# pedalBoard.net
KiCad netlist of a schematic drawn in EAGLE
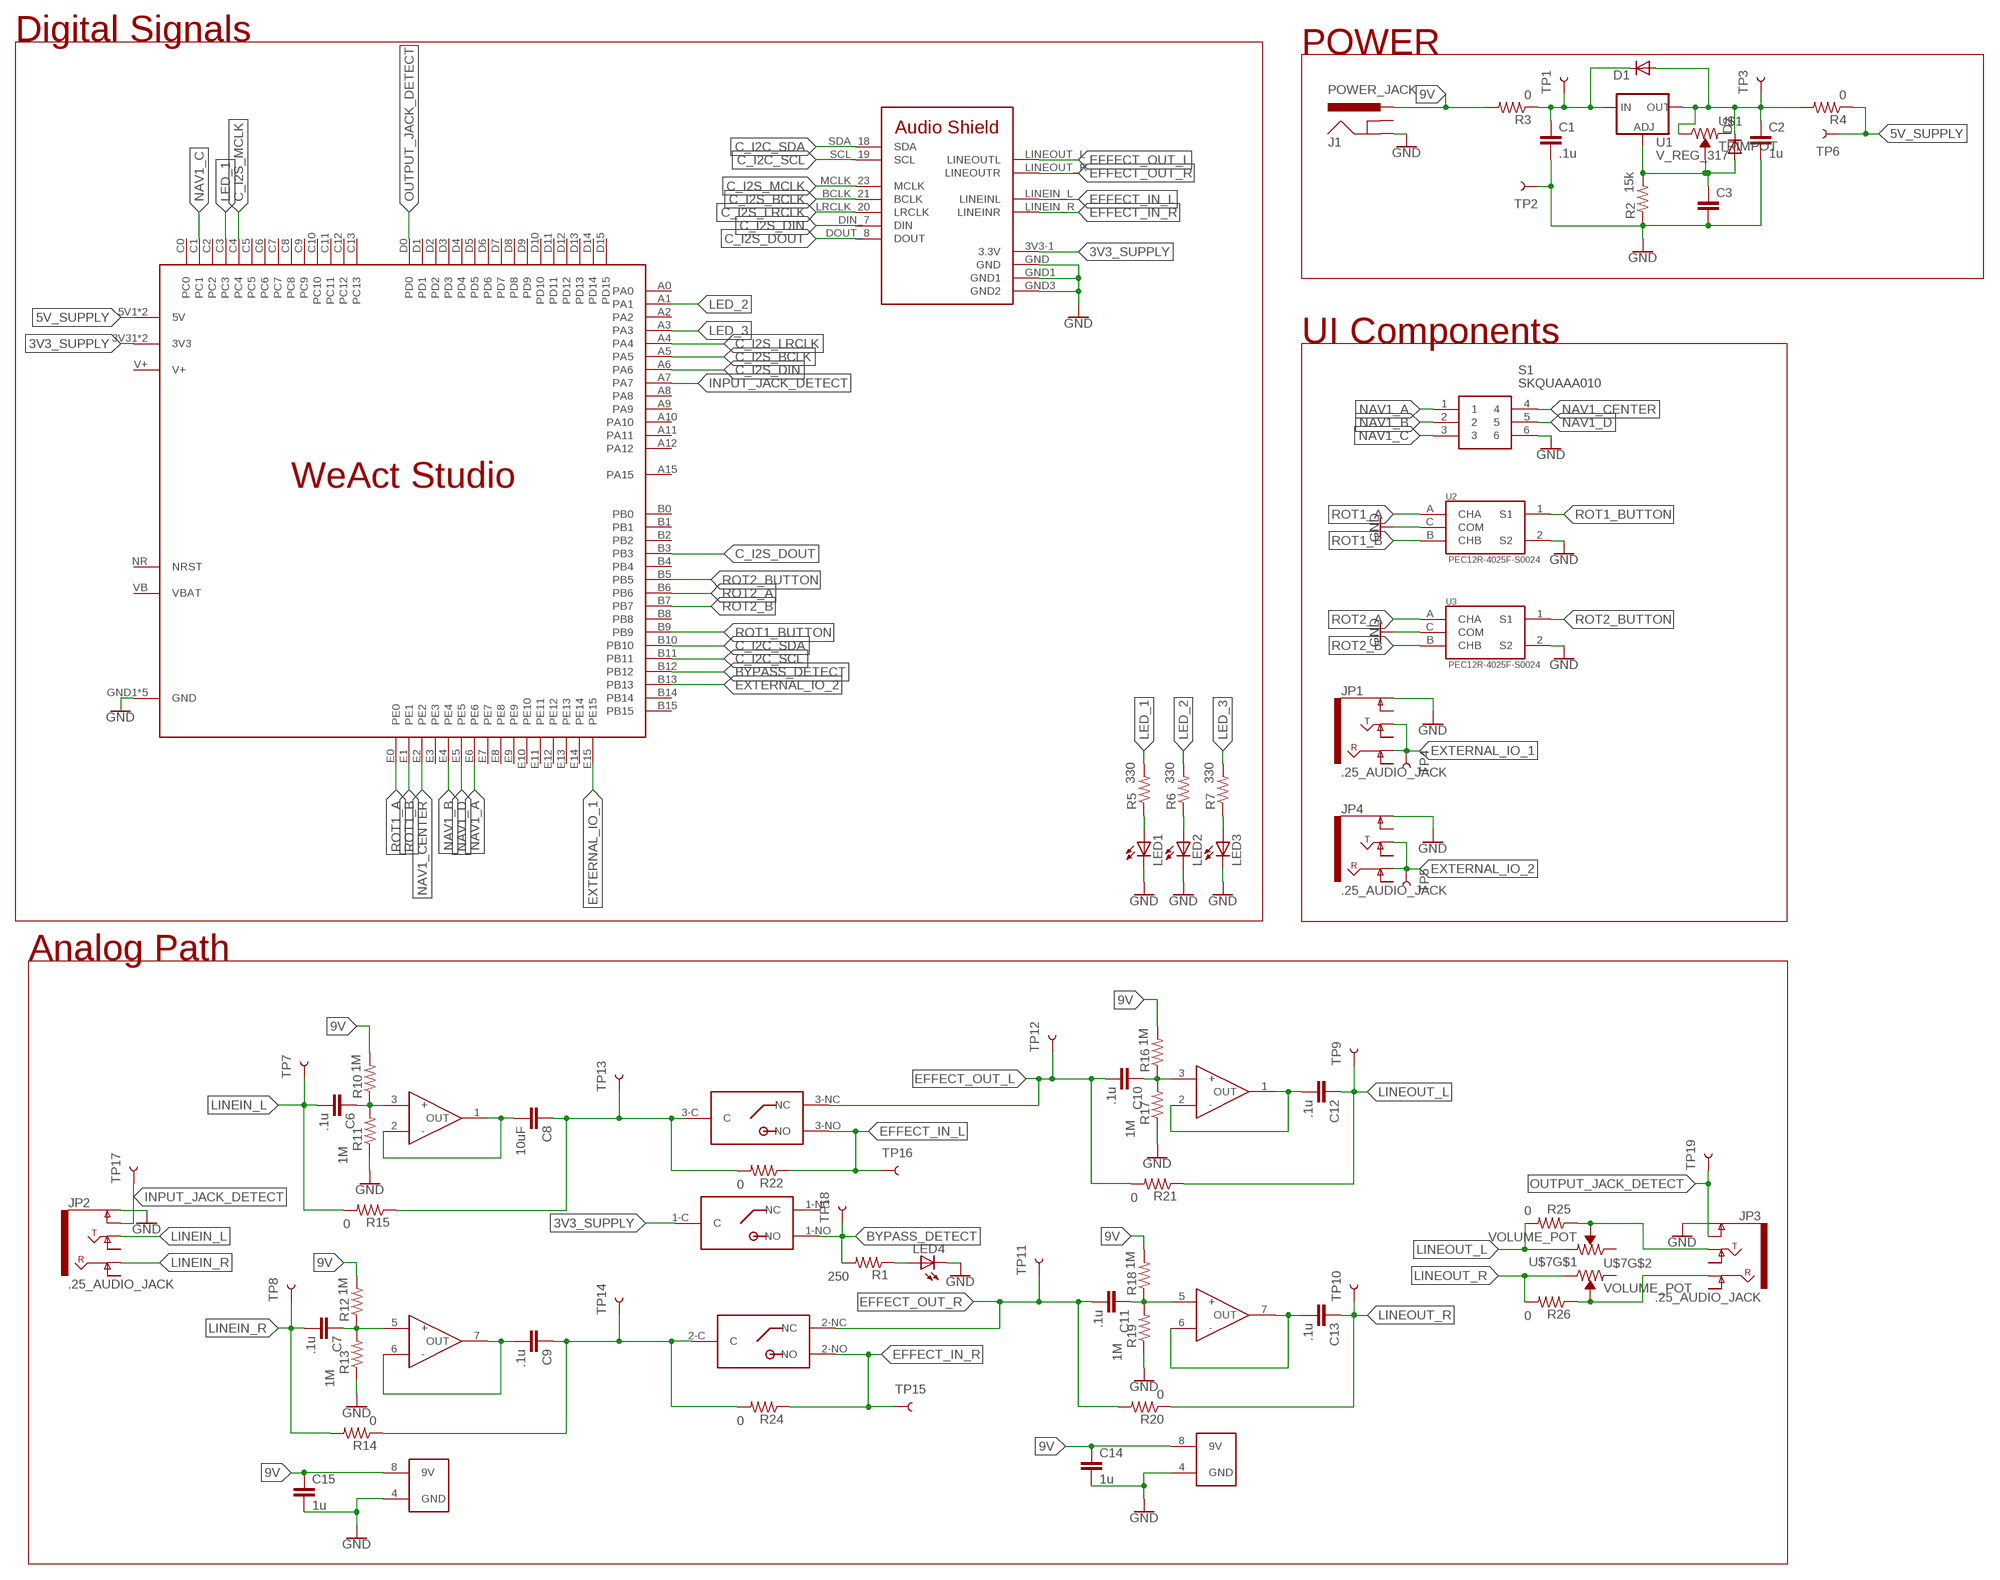
[diagram p0: schematic, sheet 1]

(export (version "E")
  (design (tool "Eeschema 10.0.6"))
  (components
    (comp (ref "C1")
      (value ".1u")
      (footprint "eagle-import:C5B3")
      (libsource (lib "eagle-import") (part "C5/3"))
    )
    (comp (ref "C2")
      (value "1u")
      (footprint "eagle-import:C5B3")
      (libsource (lib "eagle-import") (part "C5/3"))
    )
    (comp (ref "C3")
      (value "C5/3")
      (footprint "eagle-import:C5B3")
      (libsource (lib "eagle-import") (part "C5/3"))
    )
    (comp (ref "C6")
      (value ".1u")
      (footprint "eagle-import:C5B3")
      (libsource (lib "eagle-import") (part "C5/3"))
    )
    (comp (ref "C7")
      (value ".1u")
      (footprint "eagle-import:C5B3")
      (libsource (lib "eagle-import") (part "C5/3"))
    )
    (comp (ref "C8")
      (value "10uF")
      (footprint "eagle-import:C5B3")
      (libsource (lib "eagle-import") (part "C5/3"))
    )
    (comp (ref "C9")
      (value ".1u")
      (footprint "eagle-import:C5B3")
      (libsource (lib "eagle-import") (part "C5/3"))
    )
    (comp (ref "C10")
      (value ".1u")
      (footprint "eagle-import:C5B3")
      (libsource (lib "eagle-import") (part "C5/3"))
    )
    (comp (ref "C11")
      (value ".1u")
      (footprint "eagle-import:C5B3")
      (libsource (lib "eagle-import") (part "C5/3"))
    )
    (comp (ref "C12")
      (value ".1u")
      (footprint "eagle-import:C5B3")
      (libsource (lib "eagle-import") (part "C5/3"))
    )
    (comp (ref "C13")
      (value ".1u")
      (footprint "eagle-import:C5B3")
      (libsource (lib "eagle-import") (part "C5/3"))
    )
    (comp (ref "C14")
      (value "1u")
      (footprint "eagle-import:C5B3")
      (libsource (lib "eagle-import") (part "C5/3"))
    )
    (comp (ref "C15")
      (value "1u")
      (footprint "eagle-import:C5B3")
      (libsource (lib "eagle-import") (part "C5/3"))
    )
    (comp (ref "D1")
      (value "1N4004")
      (footprint "eagle-import:DO41-10")
      (libsource (lib "eagle-import") (part "1N4004"))
    )
    (comp (ref "D2")
      (value "1N4004")
      (footprint "eagle-import:DO41-10")
      (libsource (lib "eagle-import") (part "1N4004"))
    )
    (comp (ref "J1")
      (value "POWER_JACK")
      (footprint "eagle-import:POWER_JACK_PTH")
      (libsource (lib "eagle-import") (part "POWER_JACK"))
    )
    (comp (ref "JP1")
      (value ".25_AUDIO_JACK")
      (footprint "eagle-import:SPARKFUN-CONNECTORS_AUDIO-JACK-.25-INCH-HORIZ-PTH")
      (libsource (lib "eagle-import") (part ".25_AUDIO_JACK"))
    )
    (comp (ref "JP2")
      (value ".25_AUDIO_JACK")
      (footprint "eagle-import:SPARKFUN-CONNECTORS_AUDIO-JACK-.25-INCH-HORIZ-PTH")
      (libsource (lib "eagle-import") (part ".25_AUDIO_JACK"))
    )
    (comp (ref "JP3")
      (value ".25_AUDIO_JACK")
      (footprint "eagle-import:SPARKFUN-CONNECTORS_AUDIO-JACK-.25-INCH-HORIZ-PTH")
      (libsource (lib "eagle-import") (part ".25_AUDIO_JACK"))
    )
    (comp (ref "JP4")
      (value ".25_AUDIO_JACK")
      (footprint "eagle-import:SPARKFUN-CONNECTORS_AUDIO-JACK-.25-INCH-HORIZ-PTH")
      (libsource (lib "eagle-import") (part ".25_AUDIO_JACK"))
    )
    (comp (ref "LED1")
      (value "LED3MM")
      (footprint "eagle-import:LED3MM")
      (libsource (lib "eagle-import") (part "LED3MM"))
    )
    (comp (ref "LED2")
      (value "LED3MM")
      (footprint "eagle-import:LED3MM")
      (libsource (lib "eagle-import") (part "LED3MM"))
    )
    (comp (ref "LED3")
      (value "LED3MM")
      (footprint "eagle-import:LED3MM")
      (libsource (lib "eagle-import") (part "LED3MM"))
    )
    (comp (ref "LED4")
      (value "LED3MM")
      (footprint "eagle-import:LED3MM")
      (libsource (lib "eagle-import") (part "LED3MM"))
    )
    (comp (ref "R1")
      (value "250")
      (footprint "eagle-import:ADAFRUIT_0309_12")
      (libsource (lib "eagle-import") (part "ADAFRUIT_R-US_0309/12"))
    )
    (comp (ref "R2")
      (value "15k")
      (footprint "eagle-import:ADAFRUIT_0309_12")
      (libsource (lib "eagle-import") (part "ADAFRUIT_R-US_0309/12"))
    )
    (comp (ref "R3")
      (value "0")
      (footprint "eagle-import:ADAFRUIT_0309_12")
      (libsource (lib "eagle-import") (part "ADAFRUIT_R-US_0309/12"))
    )
    (comp (ref "R4")
      (value "0")
      (footprint "eagle-import:ADAFRUIT_0309_12")
      (libsource (lib "eagle-import") (part "ADAFRUIT_R-US_0309/12"))
    )
    (comp (ref "R5")
      (value "330")
      (footprint "eagle-import:ADAFRUIT_0309_12")
      (libsource (lib "eagle-import") (part "ADAFRUIT_R-US_0309/12"))
    )
    (comp (ref "R6")
      (value "330")
      (footprint "eagle-import:ADAFRUIT_0309_12")
      (libsource (lib "eagle-import") (part "ADAFRUIT_R-US_0309/12"))
    )
    (comp (ref "R7")
      (value "330")
      (footprint "eagle-import:ADAFRUIT_0309_12")
      (libsource (lib "eagle-import") (part "ADAFRUIT_R-US_0309/12"))
    )
    (comp (ref "R10")
      (value "1M")
      (footprint "eagle-import:ADAFRUIT_0309_12")
      (libsource (lib "eagle-import") (part "ADAFRUIT_R-US_0309/12"))
    )
    (comp (ref "R11")
      (value "1M")
      (footprint "eagle-import:ADAFRUIT_0309_12")
      (libsource (lib "eagle-import") (part "ADAFRUIT_R-US_0309/12"))
    )
    (comp (ref "R12")
      (value "1M")
      (footprint "eagle-import:ADAFRUIT_0309_12")
      (libsource (lib "eagle-import") (part "ADAFRUIT_R-US_0309/12"))
    )
    (comp (ref "R13")
      (value "1M")
      (footprint "eagle-import:ADAFRUIT_0309_12")
      (libsource (lib "eagle-import") (part "ADAFRUIT_R-US_0309/12"))
    )
    (comp (ref "R14")
      (value "0")
      (footprint "eagle-import:ADAFRUIT_0309_12")
      (libsource (lib "eagle-import") (part "ADAFRUIT_R-US_0309/12"))
    )
    (comp (ref "R15")
      (value "0")
      (footprint "eagle-import:ADAFRUIT_0309_12")
      (libsource (lib "eagle-import") (part "ADAFRUIT_R-US_0309/12"))
    )
    (comp (ref "R16")
      (value "1M")
      (footprint "eagle-import:ADAFRUIT_0309_12")
      (libsource (lib "eagle-import") (part "ADAFRUIT_R-US_0309/12"))
    )
    (comp (ref "R17")
      (value "1M")
      (footprint "eagle-import:ADAFRUIT_0309_12")
      (libsource (lib "eagle-import") (part "ADAFRUIT_R-US_0309/12"))
    )
    (comp (ref "R18")
      (value "1M")
      (footprint "eagle-import:ADAFRUIT_0309_12")
      (libsource (lib "eagle-import") (part "ADAFRUIT_R-US_0309/12"))
    )
    (comp (ref "R19")
      (value "1M")
      (footprint "eagle-import:ADAFRUIT_0309_12")
      (libsource (lib "eagle-import") (part "ADAFRUIT_R-US_0309/12"))
    )
    (comp (ref "R20")
      (value "0")
      (footprint "eagle-import:ADAFRUIT_0309_12")
      (libsource (lib "eagle-import") (part "ADAFRUIT_R-US_0309/12"))
    )
    (comp (ref "R21")
      (value "0")
      (footprint "eagle-import:ADAFRUIT_0309_12")
      (libsource (lib "eagle-import") (part "ADAFRUIT_R-US_0309/12"))
    )
    (comp (ref "R22")
      (value "0")
      (footprint "eagle-import:ADAFRUIT_0309_12")
      (libsource (lib "eagle-import") (part "ADAFRUIT_R-US_0309/12"))
    )
    (comp (ref "R24")
      (value "0")
      (footprint "eagle-import:ADAFRUIT_0309_12")
      (libsource (lib "eagle-import") (part "ADAFRUIT_R-US_0309/12"))
    )
    (comp (ref "R25")
      (value "0")
      (footprint "eagle-import:ADAFRUIT_0309_12")
      (libsource (lib "eagle-import") (part "ADAFRUIT_R-US_0309/12"))
    )
    (comp (ref "R26")
      (value "0")
      (footprint "eagle-import:ADAFRUIT_0309_12")
      (libsource (lib "eagle-import") (part "ADAFRUIT_R-US_0309/12"))
    )
    (comp (ref "S1")
      (value "SKQUAAA010")
      (footprint "eagle-import:SKQUAAA010")
      (fields (field (name "MOUSER_PART_NUMBER") "688-SKQUAA"))
      (libsource (lib "eagle-import") (part "SKQUAAA010"))
    )
    (comp (ref "TP1")
      (value "TEST-POINT3X5")
      (footprint "eagle-import:PAD.03X.05")
      (libsource (lib "eagle-import") (part "TEST-POINT3X5"))
    )
    (comp (ref "TP2")
      (value "TEST-POINT3X5")
      (footprint "eagle-import:PAD.03X.05")
      (libsource (lib "eagle-import") (part "TEST-POINT3X5"))
    )
    (comp (ref "TP3")
      (value "TEST-POINT3X5")
      (footprint "eagle-import:PAD.03X.05")
      (libsource (lib "eagle-import") (part "TEST-POINT3X5"))
    )
    (comp (ref "TP4")
      (value "TEST-POINT3X5")
      (footprint "eagle-import:PAD.03X.05")
      (libsource (lib "eagle-import") (part "TEST-POINT3X5"))
    )
    (comp (ref "TP5")
      (value "TEST-POINT3X5")
      (footprint "eagle-import:PAD.03X.05")
      (libsource (lib "eagle-import") (part "TEST-POINT3X5"))
    )
    (comp (ref "TP6")
      (value "TEST-POINT3X5")
      (footprint "eagle-import:PAD.03X.05")
      (libsource (lib "eagle-import") (part "TEST-POINT3X5"))
    )
    (comp (ref "TP7")
      (value "TEST-POINT3X5")
      (footprint "eagle-import:PAD.03X.05")
      (libsource (lib "eagle-import") (part "TEST-POINT3X5"))
    )
    (comp (ref "TP8")
      (value "TEST-POINT3X5")
      (footprint "eagle-import:PAD.03X.05")
      (libsource (lib "eagle-import") (part "TEST-POINT3X5"))
    )
    (comp (ref "TP9")
      (value "TEST-POINT3X5")
      (footprint "eagle-import:PAD.03X.05")
      (libsource (lib "eagle-import") (part "TEST-POINT3X5"))
    )
    (comp (ref "TP10")
      (value "TEST-POINT3X5")
      (footprint "eagle-import:PAD.03X.05")
      (libsource (lib "eagle-import") (part "TEST-POINT3X5"))
    )
    (comp (ref "TP11")
      (value "TEST-POINT3X5")
      (footprint "eagle-import:PAD.03X.05")
      (libsource (lib "eagle-import") (part "TEST-POINT3X5"))
    )
    (comp (ref "TP12")
      (value "TEST-POINT3X5")
      (footprint "eagle-import:PAD.03X.05")
      (libsource (lib "eagle-import") (part "TEST-POINT3X5"))
    )
    (comp (ref "TP13")
      (value "TEST-POINT3X5")
      (footprint "eagle-import:PAD.03X.05")
      (libsource (lib "eagle-import") (part "TEST-POINT3X5"))
    )
    (comp (ref "TP14")
      (value "TEST-POINT3X5")
      (footprint "eagle-import:PAD.03X.05")
      (libsource (lib "eagle-import") (part "TEST-POINT3X5"))
    )
    (comp (ref "TP15")
      (value "TEST-POINT3X5")
      (footprint "eagle-import:PAD.03X.05")
      (libsource (lib "eagle-import") (part "TEST-POINT3X5"))
    )
    (comp (ref "TP16")
      (value "TEST-POINT3X5")
      (footprint "eagle-import:PAD.03X.05")
      (libsource (lib "eagle-import") (part "TEST-POINT3X5"))
    )
    (comp (ref "TP17")
      (value "TEST-POINT3X5")
      (footprint "eagle-import:PAD.03X.05")
      (libsource (lib "eagle-import") (part "TEST-POINT3X5"))
    )
    (comp (ref "TP18")
      (value "TEST-POINT3X5")
      (footprint "eagle-import:PAD.03X.05")
      (libsource (lib "eagle-import") (part "TEST-POINT3X5"))
    )
    (comp (ref "TP19")
      (value "TEST-POINT3X5")
      (footprint "eagle-import:PAD.03X.05")
      (libsource (lib "eagle-import") (part "TEST-POINT3X5"))
    )
    (comp (ref "U$1")
      (value "TRIMPOT")
      (footprint "eagle-import:TRIMPOT")
      (libsource (lib "eagle-import") (part "TRIMPOT"))
    )
    (comp (ref "U$2")
      (value "STOMP_SWITCH")
      (footprint "eagle-import:STOMP_SWITCH")
      (libsource (lib "eagle-import") (part "STOMP_SWITCH"))
    )
    (comp (ref "U$3")
      (value "AUDIO_SHIELD")
      (footprint "eagle-import:AUDIO_SHIELD")
      (libsource (lib "eagle-import") (part "AUDIO_SHIELD"))
    )
    (comp (ref "U$4")
      (value "WEACT_STUDIO")
      (footprint "eagle-import:WEACT_STUDIO")
      (libsource (lib "eagle-import") (part "WEACT_STUDIO"))
    )
    (comp (ref "U$5")
      (value "TL072")
      (footprint "eagle-import:8S1")
      (libsource (lib "eagle-import") (part "TL072"))
    )
    (comp (ref "U$6")
      (value "TL072")
      (footprint "eagle-import:8S1")
      (libsource (lib "eagle-import") (part "TL072"))
    )
    (comp (ref "U$7")
      (value "VOLUME_POT")
      (footprint "eagle-import:2X3")
      (libsource (lib "eagle-import") (part "VOLUME_POT"))
    )
    (comp (ref "U1")
      (value "V_REG_317")
      (footprint "eagle-import:TO220")
      (libsource (lib "eagle-import") (part "V_REG_317"))
    )
    (comp (ref "U2")
      (value "PEC12R-4025F-S0024")
      (footprint "eagle-import:ENC_PEC12R-4025F-S0024")
      (fields (field (name "MF") "Bourns"))
      (libsource (lib "eagle-import") (part "PEC12R-4025F-S0024"))
    )
    (comp (ref "U3")
      (value "PEC12R-4025F-S0024")
      (footprint "eagle-import:ENC_PEC12R-4025F-S0024")
      (fields (field (name "MF") "Bourns"))
      (libsource (lib "eagle-import") (part "PEC12R-4025F-S0024"))
    )
  )
  (nets
    (net (code "1") (name "3V3_SUPPLY") (class "Default")
      (node (ref "U$2") (pin "1-C") (pinfunction "C_1-C") (pintype "bidirectional"))
      (node (ref "U$3") (pin "3V3-1") (pinfunction "3.3V_3V3-1") (pintype "bidirectional"))
      (node (ref "U$4") (pin "3V31") (pinfunction "3V3_3V31") (pintype "bidirectional"))
      (node (ref "U$4") (pin "3V32") (pinfunction "3V3_3V32") (pintype "bidirectional"))
    )
    (net (code "2") (name "5V_SUPPLY") (class "Default")
      (node (ref "R4") (pin "1") (pinfunction "1_1") (pintype "passive"))
      (node (ref "TP6") (pin "P$1") (pinfunction "1_P$1") (pintype "bidirectional"))
      (node (ref "U$4") (pin "5V1") (pinfunction "5V_5V1") (pintype "bidirectional"))
      (node (ref "U$4") (pin "5V2") (pinfunction "5V_5V2") (pintype "bidirectional"))
    )
    (net (code "3") (name "9V") (class "Default")
      (node (ref "C14") (pin "1") (pinfunction "1_1") (pintype "passive"))
      (node (ref "C15") (pin "1") (pinfunction "1_1") (pintype "passive"))
      (node (ref "J1") (pin "GND") (pinfunction "PWR_GND") (pintype "bidirectional"))
      (node (ref "R10") (pin "2") (pinfunction "2_2") (pintype "passive"))
      (node (ref "R12") (pin "2") (pinfunction "2_2") (pintype "passive"))
      (node (ref "R16") (pin "2") (pinfunction "2_2") (pintype "passive"))
      (node (ref "R18") (pin "2") (pinfunction "2_2") (pintype "passive"))
      (node (ref "R3") (pin "2") (pinfunction "2_2") (pintype "passive"))
      (node (ref "U$5") (pin "8") (pinfunction "9V_8") (pintype "bidirectional"))
      (node (ref "U$6") (pin "8") (pinfunction "9V_8") (pintype "bidirectional"))
    )
    (net (code "4") (name "BYPASS_DETECT") (class "Default")
      (node (ref "R1") (pin "2") (pinfunction "2_2") (pintype "passive"))
      (node (ref "TP18") (pin "P$1") (pinfunction "1_P$1") (pintype "bidirectional"))
      (node (ref "U$2") (pin "1-NO") (pinfunction "NO_1-NO") (pintype "bidirectional"))
      (node (ref "U$4") (pin "B12") (pinfunction "PB12_B12") (pintype "bidirectional"))
    )
    (net (code "5") (name "C_I2C_SCL") (class "Default")
      (node (ref "U$3") (pin "SCL_19") (pinfunction "SCL_SCL_19") (pintype "bidirectional"))
      (node (ref "U$4") (pin "B11") (pinfunction "PB11_B11") (pintype "bidirectional"))
    )
    (net (code "6") (name "C_I2C_SDA") (class "Default")
      (node (ref "U$3") (pin "SDA_18") (pinfunction "SDA_SDA_18") (pintype "bidirectional"))
      (node (ref "U$4") (pin "B10") (pinfunction "PB10_B10") (pintype "bidirectional"))
    )
    (net (code "7") (name "C_I2S_BCLK") (class "Default")
      (node (ref "U$3") (pin "BCLK_21") (pinfunction "BCLK_BCLK_21") (pintype "bidirectional"))
      (node (ref "U$4") (pin "A5") (pinfunction "PA5_A5") (pintype "bidirectional"))
    )
    (net (code "8") (name "C_I2S_DIN") (class "Default")
      (node (ref "U$3") (pin "DIN_7") (pinfunction "DIN_DIN_7") (pintype "bidirectional"))
      (node (ref "U$4") (pin "A6") (pinfunction "PA6_A6") (pintype "bidirectional"))
    )
    (net (code "9") (name "C_I2S_DOUT") (class "Default")
      (node (ref "U$3") (pin "DOUT_8") (pinfunction "DOUT_DOUT_8") (pintype "bidirectional"))
      (node (ref "U$4") (pin "B3") (pinfunction "PB3_B3") (pintype "bidirectional"))
    )
    (net (code "10") (name "C_I2S_LRCLK") (class "Default")
      (node (ref "U$3") (pin "LRCLK_20") (pinfunction "LRCLK_LRCLK_20") (pintype "bidirectional"))
      (node (ref "U$4") (pin "A4") (pinfunction "PA4_A4") (pintype "bidirectional"))
    )
    (net (code "11") (name "C_I2S_MCLK") (class "Default")
      (node (ref "U$3") (pin "MCLK_23") (pinfunction "MCLK_MCLK_23") (pintype "bidirectional"))
      (node (ref "U$4") (pin "C4") (pinfunction "PC4_C4") (pintype "bidirectional"))
    )
    (net (code "12") (name "EFFECT_IN_L") (class "Default")
      (node (ref "R22") (pin "1") (pinfunction "1_1") (pintype "passive"))
      (node (ref "TP16") (pin "P$1") (pinfunction "1_P$1") (pintype "bidirectional"))
      (node (ref "U$2") (pin "3-NO") (pinfunction "NO_3-NO") (pintype "bidirectional"))
      (node (ref "U$3") (pin "LINEIN_L") (pinfunction "LINEINL_LINEIN_L") (pintype "bidirectional"))
    )
    (net (code "13") (name "EFFECT_IN_R") (class "Default")
      (node (ref "R24") (pin "1") (pinfunction "1_1") (pintype "passive"))
      (node (ref "TP15") (pin "P$1") (pinfunction "1_P$1") (pintype "bidirectional"))
      (node (ref "U$2") (pin "2-NO") (pinfunction "NO_2-NO") (pintype "bidirectional"))
      (node (ref "U$3") (pin "LINEIN_R") (pinfunction "LINEINR_LINEIN_R") (pintype "bidirectional"))
    )
    (net (code "14") (name "EFFECT_OUT_L") (class "Default")
      (node (ref "C10") (pin "2") (pinfunction "2_2") (pintype "passive"))
      (node (ref "R21") (pin "2") (pinfunction "2_2") (pintype "passive"))
      (node (ref "TP12") (pin "P$1") (pinfunction "1_P$1") (pintype "bidirectional"))
      (node (ref "U$2") (pin "3-NC") (pinfunction "NC_3-NC") (pintype "bidirectional"))
      (node (ref "U$3") (pin "LINEOUT_L") (pinfunction "LINEOUTL_LINEOUT_L") (pintype "bidirectional"))
    )
    (net (code "15") (name "EFFECT_OUT_R") (class "Default")
      (node (ref "C11") (pin "2") (pinfunction "2_2") (pintype "passive"))
      (node (ref "R20") (pin "2") (pinfunction "2_2") (pintype "passive"))
      (node (ref "TP11") (pin "P$1") (pinfunction "1_P$1") (pintype "bidirectional"))
      (node (ref "U$2") (pin "2-NC") (pinfunction "NC_2-NC") (pintype "bidirectional"))
      (node (ref "U$3") (pin "LINEOUT_R") (pinfunction "LINEOUTR_LINEOUT_R") (pintype "bidirectional"))
    )
    (net (code "16") (name "EXTERNAL_IO_1") (class "Default")
      (node (ref "JP1") (pin "RING") (pinfunction "RING_RING") (pintype "bidirectional"))
      (node (ref "JP1") (pin "TIP") (pinfunction "TIP_TIP") (pintype "bidirectional"))
      (node (ref "TP4") (pin "P$1") (pinfunction "1_P$1") (pintype "bidirectional"))
      (node (ref "U$4") (pin "E15") (pinfunction "PE15_E15") (pintype "bidirectional"))
    )
    (net (code "17") (name "EXTERNAL_IO_2") (class "Default")
      (node (ref "JP4") (pin "RING") (pinfunction "RING_RING") (pintype "bidirectional"))
      (node (ref "JP4") (pin "TIP") (pinfunction "TIP_TIP") (pintype "bidirectional"))
      (node (ref "TP5") (pin "P$1") (pinfunction "1_P$1") (pintype "bidirectional"))
      (node (ref "U$4") (pin "B13") (pinfunction "PB13_B13") (pintype "bidirectional"))
    )
    (net (code "18") (name "GND") (class "Default")
      (node (ref "C1") (pin "2") (pinfunction "2_2") (pintype "passive"))
      (node (ref "C14") (pin "2") (pinfunction "2_2") (pintype "passive"))
      (node (ref "C15") (pin "2") (pinfunction "2_2") (pintype "passive"))
      (node (ref "C2") (pin "2") (pinfunction "2_2") (pintype "passive"))
      (node (ref "C3") (pin "2") (pinfunction "2_2") (pintype "passive"))
      (node (ref "J1") (pin "PWR") (pinfunction "GND_PWR") (pintype "bidirectional"))
      (node (ref "JP1") (pin "SLEEVE") (pinfunction "EARTH_SLEEVE") (pintype "bidirectional"))
      (node (ref "JP2") (pin "SLEEVE") (pinfunction "EARTH_SLEEVE") (pintype "bidirectional"))
      (node (ref "JP3") (pin "SLEEVE") (pinfunction "EARTH_SLEEVE") (pintype "bidirectional"))
      (node (ref "JP4") (pin "SLEEVE") (pinfunction "EARTH_SLEEVE") (pintype "bidirectional"))
      (node (ref "LED1") (pin "K") (pinfunction "C_K") (pintype "passive"))
      (node (ref "LED2") (pin "K") (pinfunction "C_K") (pintype "passive"))
      (node (ref "LED3") (pin "K") (pinfunction "C_K") (pintype "passive"))
      (node (ref "LED4") (pin "K") (pinfunction "C_K") (pintype "passive"))
      (node (ref "R11") (pin "1") (pinfunction "1_1") (pintype "passive"))
      (node (ref "R13") (pin "1") (pinfunction "1_1") (pintype "passive"))
      (node (ref "R17") (pin "1") (pinfunction "1_1") (pintype "passive"))
      (node (ref "R19") (pin "1") (pinfunction "1_1") (pintype "passive"))
      (node (ref "R2") (pin "1") (pinfunction "1_1") (pintype "passive"))
      (node (ref "S1") (pin "6") (pinfunction "6_6") (pintype "bidirectional"))
      (node (ref "TP2") (pin "P$1") (pinfunction "1_P$1") (pintype "bidirectional"))
      (node (ref "U$3") (pin "GND") (pinfunction "GND_GND") (pintype "bidirectional"))
      (node (ref "U$3") (pin "GND1") (pinfunction "GND1_GND1") (pintype "bidirectional"))
      (node (ref "U$3") (pin "GND3") (pinfunction "GND2_GND3") (pintype "bidirectional"))
      (node (ref "U$4") (pin "GND1") (pinfunction "GND_GND1") (pintype "bidirectional"))
      (node (ref "U$4") (pin "GND2") (pinfunction "GND_GND2") (pintype "bidirectional"))
      (node (ref "U$4") (pin "GND3") (pinfunction "GND_GND3") (pintype "bidirectional"))
      (node (ref "U$4") (pin "GND4") (pinfunction "GND_GND4") (pintype "bidirectional"))
      (node (ref "U$4") (pin "GND5") (pinfunction "GND_GND5") (pintype "bidirectional"))
      (node (ref "U$5") (pin "4") (pinfunction "GND_4") (pintype "bidirectional"))
      (node (ref "U$6") (pin "4") (pinfunction "GND_4") (pintype "bidirectional"))
      (node (ref "U2") (pin "2") (pinfunction "S2_2") (pintype "passive"))
      (node (ref "U2") (pin "C") (pinfunction "COM_C") (pintype "bidirectional"))
      (node (ref "U3") (pin "2") (pinfunction "S2_2") (pintype "passive"))
      (node (ref "U3") (pin "C") (pinfunction "COM_C") (pintype "bidirectional"))
    )
    (net (code "19") (name "INPUT_JACK_DETECT") (class "Default")
      (node (ref "JP2") (pin "SLEEVE-NORM") (pinfunction "EARTH-NORM_SLEEVE-NORM") (pintype "bidirectional"))
      (node (ref "TP17") (pin "P$1") (pinfunction "1_P$1") (pintype "bidirectional"))
      (node (ref "U$4") (pin "A7") (pinfunction "PA7_A7") (pintype "bidirectional"))
    )
    (net (code "20") (name "LED_1") (class "Default")
      (node (ref "R5") (pin "2") (pinfunction "2_2") (pintype "passive"))
      (node (ref "U$4") (pin "C3") (pinfunction "PC3_C3") (pintype "bidirectional"))
    )
    (net (code "21") (name "LED_2") (class "Default")
      (node (ref "R6") (pin "2") (pinfunction "2_2") (pintype "passive"))
      (node (ref "U$4") (pin "A1") (pinfunction "PA1_A1") (pintype "bidirectional"))
    )
    (net (code "22") (name "LED_3") (class "Default")
      (node (ref "R7") (pin "2") (pinfunction "2_2") (pintype "passive"))
      (node (ref "U$4") (pin "A3") (pinfunction "PA3_A3") (pintype "bidirectional"))
    )
    (net (code "23") (name "LINEIN_L") (class "Default")
      (node (ref "C6") (pin "2") (pinfunction "2_2") (pintype "passive"))
      (node (ref "JP2") (pin "TIP") (pinfunction "TIP_TIP") (pintype "bidirectional"))
      (node (ref "R15") (pin "2") (pinfunction "2_2") (pintype "passive"))
      (node (ref "TP7") (pin "P$1") (pinfunction "1_P$1") (pintype "bidirectional"))
    )
    (net (code "24") (name "LINEIN_R") (class "Default")
      (node (ref "C7") (pin "2") (pinfunction "2_2") (pintype "passive"))
      (node (ref "JP2") (pin "RING") (pinfunction "RING_RING") (pintype "bidirectional"))
      (node (ref "R14") (pin "2") (pinfunction "2_2") (pintype "passive"))
      (node (ref "TP8") (pin "P$1") (pinfunction "1_P$1") (pintype "bidirectional"))
    )
    (net (code "25") (name "LINEOUT_L") (class "Default")
      (node (ref "C12") (pin "1") (pinfunction "1_1") (pintype "passive"))
      (node (ref "JP3") (pin "TIP") (pinfunction "TIP_TIP") (pintype "bidirectional"))
      (node (ref "R21") (pin "1") (pinfunction "1_1") (pintype "passive"))
      (node (ref "R25") (pin "1") (pinfunction "1_1") (pintype "passive"))
      (node (ref "TP9") (pin "P$1") (pinfunction "1_P$1") (pintype "bidirectional"))
      (node (ref "U$7") (pin "2") (pinfunction "WIPER_2") (pintype "passive"))
    )
    (net (code "26") (name "LINEOUT_R") (class "Default")
      (node (ref "C13") (pin "1") (pinfunction "1_1") (pintype "passive"))
      (node (ref "JP3") (pin "RING") (pinfunction "RING_RING") (pintype "bidirectional"))
      (node (ref "R20") (pin "1") (pinfunction "1_1") (pintype "passive"))
      (node (ref "R26") (pin "1") (pinfunction "1_1") (pintype "passive"))
      (node (ref "TP10") (pin "P$1") (pinfunction "1_P$1") (pintype "bidirectional"))
      (node (ref "U$7") (pin "5") (pinfunction "WIPER_5") (pintype "passive"))
    )
    (net (code "27") (name "NAV1_A") (class "Default")
      (node (ref "S1") (pin "1") (pinfunction "1_1") (pintype "bidirectional"))
      (node (ref "U$4") (pin "E6") (pinfunction "PE6_E6") (pintype "bidirectional"))
    )
    (net (code "28") (name "NAV1_B") (class "Default")
      (node (ref "S1") (pin "2") (pinfunction "2_2") (pintype "bidirectional"))
      (node (ref "U$4") (pin "E4") (pinfunction "PE4_E4") (pintype "bidirectional"))
    )
    (net (code "29") (name "NAV1_C") (class "Default")
      (node (ref "S1") (pin "3") (pinfunction "3_3") (pintype "bidirectional"))
      (node (ref "U$4") (pin "C1") (pinfunction "PC1_C1") (pintype "bidirectional"))
    )
    (net (code "30") (name "NAV1_CENTER") (class "Default")
      (node (ref "S1") (pin "4") (pinfunction "4_4") (pintype "bidirectional"))
      (node (ref "U$4") (pin "E2") (pinfunction "PE2_E2") (pintype "bidirectional"))
    )
    (net (code "31") (name "NAV1_D") (class "Default")
      (node (ref "S1") (pin "5") (pinfunction "5_5") (pintype "bidirectional"))
      (node (ref "U$4") (pin "E5") (pinfunction "PE5_E5") (pintype "bidirectional"))
    )
    (net (code "32") (name "Net-(LED1-PadA)") (class "Default")
      (node (ref "LED1") (pin "A") (pinfunction "A_A") (pintype "passive"))
      (node (ref "R5") (pin "1") (pinfunction "1_1") (pintype "passive"))
    )
    (net (code "33") (name "Net-(LED2-PadA)") (class "Default")
      (node (ref "LED2") (pin "A") (pinfunction "A_A") (pintype "passive"))
      (node (ref "R6") (pin "1") (pinfunction "1_1") (pintype "passive"))
    )
    (net (code "34") (name "Net-(LED3-PadA)") (class "Default")
      (node (ref "LED3") (pin "A") (pinfunction "A_A") (pintype "passive"))
      (node (ref "R7") (pin "1") (pinfunction "1_1") (pintype "passive"))
    )
    (net (code "35") (name "Net-(LED4-PadA)") (class "Default")
      (node (ref "LED4") (pin "A") (pinfunction "A_A") (pintype "passive"))
      (node (ref "R1") (pin "1") (pinfunction "1_1") (pintype "passive"))
    )
    (net (code "36") (name "Net-(TP1-1)") (class "Default")
      (node (ref "C1") (pin "1") (pinfunction "1_1") (pintype "passive"))
      (node (ref "D1") (pin "C") (pinfunction "C_C") (pintype "passive"))
      (node (ref "R3") (pin "1") (pinfunction "1_1") (pintype "passive"))
      (node (ref "TP1") (pin "P$1") (pinfunction "1_P$1") (pintype "bidirectional"))
      (node (ref "U1") (pin "3") (pinfunction "IN_3") (pintype "input"))
    )
    (net (code "37") (name "Net-(TP3-1)") (class "Default")
      (node (ref "C2") (pin "1") (pinfunction "1_1") (pintype "passive"))
      (node (ref "D1") (pin "A") (pinfunction "A_A") (pintype "passive"))
      (node (ref "D2") (pin "C") (pinfunction "C_C") (pintype "passive"))
      (node (ref "R4") (pin "2") (pinfunction "2_2") (pintype "passive"))
      (node (ref "TP3") (pin "P$1") (pinfunction "1_P$1") (pintype "bidirectional"))
      (node (ref "U$1") (pin "P$2") (pinfunction "CW_P$2") (pintype "passive"))
      (node (ref "U1") (pin "2") (pinfunction "OUT_2") (pintype "output"))
    )
    (net (code "38") (name "Net-(TP13-1)") (class "Default")
      (node (ref "C8") (pin "1") (pinfunction "1_1") (pintype "passive"))
      (node (ref "R15") (pin "1") (pinfunction "1_1") (pintype "passive"))
      (node (ref "R22") (pin "2") (pinfunction "2_2") (pintype "passive"))
      (node (ref "TP13") (pin "P$1") (pinfunction "1_P$1") (pintype "bidirectional"))
      (node (ref "U$2") (pin "3-C") (pinfunction "C_3-C") (pintype "bidirectional"))
    )
    (net (code "39") (name "Net-(TP14-1)") (class "Default")
      (node (ref "C9") (pin "1") (pinfunction "1_1") (pintype "passive"))
      (node (ref "R14") (pin "1") (pinfunction "1_1") (pintype "passive"))
      (node (ref "R24") (pin "2") (pinfunction "2_2") (pintype "passive"))
      (node (ref "TP14") (pin "P$1") (pinfunction "1_P$1") (pintype "bidirectional"))
      (node (ref "U$2") (pin "2-C") (pinfunction "C_2-C") (pintype "bidirectional"))
    )
    (net (code "40") (name "Net-(U$1-WIPER)") (class "Default")
      (node (ref "C3") (pin "1") (pinfunction "1_1") (pintype "passive"))
      (node (ref "D2") (pin "A") (pinfunction "A_A") (pintype "passive"))
      (node (ref "R2") (pin "2") (pinfunction "2_2") (pintype "passive"))
      (node (ref "U$1") (pin "P$3") (pinfunction "WIPER_P$3") (pintype "passive"))
      (node (ref "U1") (pin "1") (pinfunction "ADJ_1") (pintype "input"))
    )
    (net (code "41") (name "Net-(U$5A-+)") (class "Default")
      (node (ref "C6") (pin "1") (pinfunction "1_1") (pintype "passive"))
      (node (ref "R10") (pin "1") (pinfunction "1_1") (pintype "passive"))
      (node (ref "R11") (pin "2") (pinfunction "2_2") (pintype "passive"))
      (node (ref "U$5") (pin "3") (pinfunction "+_3") (pintype "bidirectional"))
    )
    (net (code "42") (name "Net-(U$5A--)") (class "Default")
      (node (ref "C8") (pin "2") (pinfunction "2_2") (pintype "passive"))
      (node (ref "U$5") (pin "1") (pinfunction "OUT_1") (pintype "bidirectional"))
      (node (ref "U$5") (pin "2") (pinfunction "-_2") (pintype "bidirectional"))
    )
    (net (code "43") (name "Net-(U$5B-+)") (class "Default")
      (node (ref "C7") (pin "1") (pinfunction "1_1") (pintype "passive"))
      (node (ref "R12") (pin "1") (pinfunction "1_1") (pintype "passive"))
      (node (ref "R13") (pin "2") (pinfunction "2_2") (pintype "passive"))
      (node (ref "U$5") (pin "5") (pinfunction "+_5") (pintype "bidirectional"))
    )
    (net (code "44") (name "Net-(U$5B--)") (class "Default")
      (node (ref "C9") (pin "2") (pinfunction "2_2") (pintype "passive"))
      (node (ref "U$5") (pin "6") (pinfunction "-_6") (pintype "bidirectional"))
      (node (ref "U$5") (pin "7") (pinfunction "OUT_7") (pintype "bidirectional"))
    )
    (net (code "45") (name "Net-(U$6A-+)") (class "Default")
      (node (ref "C10") (pin "1") (pinfunction "1_1") (pintype "passive"))
      (node (ref "R16") (pin "1") (pinfunction "1_1") (pintype "passive"))
      (node (ref "R17") (pin "2") (pinfunction "2_2") (pintype "passive"))
      (node (ref "U$6") (pin "3") (pinfunction "+_3") (pintype "bidirectional"))
    )
    (net (code "46") (name "Net-(U$6A--)") (class "Default")
      (node (ref "C12") (pin "2") (pinfunction "2_2") (pintype "passive"))
      (node (ref "U$6") (pin "1") (pinfunction "OUT_1") (pintype "bidirectional"))
      (node (ref "U$6") (pin "2") (pinfunction "-_2") (pintype "bidirectional"))
    )
    (net (code "47") (name "Net-(U$6B-+)") (class "Default")
      (node (ref "C11") (pin "1") (pinfunction "1_1") (pintype "passive"))
      (node (ref "R18") (pin "1") (pinfunction "1_1") (pintype "passive"))
      (node (ref "R19") (pin "2") (pinfunction "2_2") (pintype "passive"))
      (node (ref "U$6") (pin "5") (pinfunction "+_5") (pintype "bidirectional"))
    )
    (net (code "48") (name "Net-(U$6B--)") (class "Default")
      (node (ref "C13") (pin "2") (pinfunction "2_2") (pintype "passive"))
      (node (ref "U$6") (pin "6") (pinfunction "-_6") (pintype "bidirectional"))
      (node (ref "U$6") (pin "7") (pinfunction "OUT_7") (pintype "bidirectional"))
    )
    (net (code "49") (name "Net-(U$7A-CCW)") (class "Default")
      (node (ref "R25") (pin "2") (pinfunction "2_2") (pintype "passive"))
      (node (ref "U$7") (pin "1") (pinfunction "CCW_1") (pintype "passive"))
    )
    (net (code "50") (name "Net-(U$7B-CW)") (class "Default")
      (node (ref "R26") (pin "2") (pinfunction "2_2") (pintype "passive"))
      (node (ref "U$7") (pin "6") (pinfunction "CW_6") (pintype "passive"))
    )
    (net (code "51") (name "OUTPUT_JACK_DETECT") (class "Default")
      (node (ref "JP3") (pin "SLEEVE-NORM") (pinfunction "EARTH-NORM_SLEEVE-NORM") (pintype "bidirectional"))
      (node (ref "TP19") (pin "P$1") (pinfunction "1_P$1") (pintype "bidirectional"))
      (node (ref "U$4") (pin "D0") (pinfunction "PD0_D0") (pintype "bidirectional"))
    )
    (net (code "52") (name "ROT1_A") (class "Default")
      (node (ref "U$4") (pin "E0") (pinfunction "PE0_E0") (pintype "bidirectional"))
      (node (ref "U2") (pin "A") (pinfunction "CHA_A") (pintype "bidirectional"))
    )
    (net (code "53") (name "ROT1_B") (class "Default")
      (node (ref "U$4") (pin "E1") (pinfunction "PE1_E1") (pintype "bidirectional"))
      (node (ref "U2") (pin "B") (pinfunction "CHB_B") (pintype "bidirectional"))
    )
    (net (code "54") (name "ROT1_BUTTON") (class "Default")
      (node (ref "U$4") (pin "B9") (pinfunction "PB9_B9") (pintype "bidirectional"))
      (node (ref "U2") (pin "1") (pinfunction "S1_1") (pintype "passive"))
    )
    (net (code "55") (name "ROT2_A") (class "Default")
      (node (ref "U$4") (pin "B6") (pinfunction "PB6_B6") (pintype "bidirectional"))
      (node (ref "U3") (pin "A") (pinfunction "CHA_A") (pintype "bidirectional"))
    )
    (net (code "56") (name "ROT2_B") (class "Default")
      (node (ref "U$4") (pin "B7") (pinfunction "PB7_B7") (pintype "bidirectional"))
      (node (ref "U3") (pin "B") (pinfunction "CHB_B") (pintype "bidirectional"))
    )
    (net (code "57") (name "ROT2_BUTTON") (class "Default")
      (node (ref "U$4") (pin "B5") (pinfunction "PB5_B5") (pintype "bidirectional"))
      (node (ref "U3") (pin "1") (pinfunction "S1_1") (pintype "passive"))
    )
    (net (code "58") (name "unconnected-(J1-PadGNDBREAK)") (class "Default")
      (node (ref "J1") (pin "GNDBREAK") (pinfunction "GNDBREAK_GNDBREAK") (pintype "bidirectional"))
    )
    (net (code "59") (name "unconnected-(JP1-EARTH-NORM-PadSLEEVE-NORM)") (class "Default")
      (node (ref "JP1") (pin "SLEEVE-NORM") (pinfunction "EARTH-NORM_SLEEVE-NORM") (pintype "bidirectional"))
    )
    (net (code "60") (name "unconnected-(JP1-PadRING-NORM)") (class "Default")
      (node (ref "JP1") (pin "RING-NORM") (pinfunction "RING-NORM_RING-NORM") (pintype "bidirectional"))
    )
    (net (code "61") (name "unconnected-(JP1-PadTIP-NORM)") (class "Default")
      (node (ref "JP1") (pin "TIP-NORM") (pinfunction "TIP-NORM_TIP-NORM") (pintype "bidirectional"))
    )
    (net (code "62") (name "unconnected-(JP2-PadRING-NORM)") (class "Default")
      (node (ref "JP2") (pin "RING-NORM") (pinfunction "RING-NORM_RING-NORM") (pintype "bidirectional"))
    )
    (net (code "63") (name "unconnected-(JP2-PadTIP-NORM)") (class "Default")
      (node (ref "JP2") (pin "TIP-NORM") (pinfunction "TIP-NORM_TIP-NORM") (pintype "bidirectional"))
    )
    (net (code "64") (name "unconnected-(JP3-PadRING-NORM)") (class "Default")
      (node (ref "JP3") (pin "RING-NORM") (pinfunction "RING-NORM_RING-NORM") (pintype "bidirectional"))
    )
    (net (code "65") (name "unconnected-(JP3-PadTIP-NORM)") (class "Default")
      (node (ref "JP3") (pin "TIP-NORM") (pinfunction "TIP-NORM_TIP-NORM") (pintype "bidirectional"))
    )
    (net (code "66") (name "unconnected-(JP4-EARTH-NORM-PadSLEEVE-NORM)") (class "Default")
      (node (ref "JP4") (pin "SLEEVE-NORM") (pinfunction "EARTH-NORM_SLEEVE-NORM") (pintype "bidirectional"))
    )
    (net (code "67") (name "unconnected-(JP4-PadRING-NORM)") (class "Default")
      (node (ref "JP4") (pin "RING-NORM") (pinfunction "RING-NORM_RING-NORM") (pintype "bidirectional"))
    )
    (net (code "68") (name "unconnected-(JP4-PadTIP-NORM)") (class "Default")
      (node (ref "JP4") (pin "TIP-NORM") (pinfunction "TIP-NORM_TIP-NORM") (pintype "bidirectional"))
    )
    (net (code "69") (name "unconnected-(U$1-CCW-PadP$1)") (class "Default")
      (node (ref "U$1") (pin "P$1") (pinfunction "CCW_P$1") (pintype "passive"))
    )
    (net (code "70") (name "unconnected-(U$2A-NC-Pad1-NC)") (class "Default")
      (node (ref "U$2") (pin "1-NC") (pinfunction "NC_1-NC") (pintype "bidirectional"))
    )
    (net (code "71") (name "unconnected-(U$4-NRST-PadNR)") (class "Default")
      (node (ref "U$4") (pin "NR") (pinfunction "NRST_NR") (pintype "bidirectional"))
    )
    (net (code "72") (name "unconnected-(U$4-PA0-PadA0)") (class "Default")
      (node (ref "U$4") (pin "A0") (pinfunction "PA0_A0") (pintype "bidirectional"))
    )
    (net (code "73") (name "unconnected-(U$4-PA2-PadA2)") (class "Default")
      (node (ref "U$4") (pin "A2") (pinfunction "PA2_A2") (pintype "bidirectional"))
    )
    (net (code "74") (name "unconnected-(U$4-PA8-PadA8)") (class "Default")
      (node (ref "U$4") (pin "A8") (pinfunction "PA8_A8") (pintype "bidirectional"))
    )
    (net (code "75") (name "unconnected-(U$4-PA9-PadA9)") (class "Default")
      (node (ref "U$4") (pin "A9") (pinfunction "PA9_A9") (pintype "bidirectional"))
    )
    (net (code "76") (name "unconnected-(U$4-PA10-PadA10)") (class "Default")
      (node (ref "U$4") (pin "A10") (pinfunction "PA10_A10") (pintype "bidirectional"))
    )
    (net (code "77") (name "unconnected-(U$4-PA11-PadA11)") (class "Default")
      (node (ref "U$4") (pin "A11") (pinfunction "PA11_A11") (pintype "bidirectional"))
    )
    (net (code "78") (name "unconnected-(U$4-PA12-PadA12)") (class "Default")
      (node (ref "U$4") (pin "A12") (pinfunction "PA12_A12") (pintype "bidirectional"))
    )
    (net (code "79") (name "unconnected-(U$4-PA15-PadA15)") (class "Default")
      (node (ref "U$4") (pin "A15") (pinfunction "PA15_A15") (pintype "bidirectional"))
    )
    (net (code "80") (name "unconnected-(U$4-PB0-PadB0)") (class "Default")
      (node (ref "U$4") (pin "B0") (pinfunction "PB0_B0") (pintype "bidirectional"))
    )
    (net (code "81") (name "unconnected-(U$4-PB1-PadB1)") (class "Default")
      (node (ref "U$4") (pin "B1") (pinfunction "PB1_B1") (pintype "bidirectional"))
    )
    (net (code "82") (name "unconnected-(U$4-PB2-PadB2)") (class "Default")
      (node (ref "U$4") (pin "B2") (pinfunction "PB2_B2") (pintype "bidirectional"))
    )
    (net (code "83") (name "unconnected-(U$4-PB4-PadB4)") (class "Default")
      (node (ref "U$4") (pin "B4") (pinfunction "PB4_B4") (pintype "bidirectional"))
    )
    (net (code "84") (name "unconnected-(U$4-PB8-PadB8)") (class "Default")
      (node (ref "U$4") (pin "B8") (pinfunction "PB8_B8") (pintype "bidirectional"))
    )
    (net (code "85") (name "unconnected-(U$4-PB14-PadB14)") (class "Default")
      (node (ref "U$4") (pin "B14") (pinfunction "PB14_B14") (pintype "bidirectional"))
    )
    (net (code "86") (name "unconnected-(U$4-PB15-PadB15)") (class "Default")
      (node (ref "U$4") (pin "B15") (pinfunction "PB15_B15") (pintype "bidirectional"))
    )
    (net (code "87") (name "unconnected-(U$4-PC0-PadC0)") (class "Default")
      (node (ref "U$4") (pin "C0") (pinfunction "PC0_C0") (pintype "bidirectional"))
    )
    (net (code "88") (name "unconnected-(U$4-PC2-PadC2)") (class "Default")
      (node (ref "U$4") (pin "C2") (pinfunction "PC2_C2") (pintype "bidirectional"))
    )
    (net (code "89") (name "unconnected-(U$4-PC5-PadC5)") (class "Default")
      (node (ref "U$4") (pin "C5") (pinfunction "PC5_C5") (pintype "bidirectional"))
    )
    (net (code "90") (name "unconnected-(U$4-PC6-PadC6)") (class "Default")
      (node (ref "U$4") (pin "C6") (pinfunction "PC6_C6") (pintype "bidirectional"))
    )
    (net (code "91") (name "unconnected-(U$4-PC7-PadC7)") (class "Default")
      (node (ref "U$4") (pin "C7") (pinfunction "PC7_C7") (pintype "bidirectional"))
    )
    (net (code "92") (name "unconnected-(U$4-PC8-PadC8)") (class "Default")
      (node (ref "U$4") (pin "C8") (pinfunction "PC8_C8") (pintype "bidirectional"))
    )
    (net (code "93") (name "unconnected-(U$4-PC9-PadC9)") (class "Default")
      (node (ref "U$4") (pin "C9") (pinfunction "PC9_C9") (pintype "bidirectional"))
    )
    (net (code "94") (name "unconnected-(U$4-PC10-PadC10)") (class "Default")
      (node (ref "U$4") (pin "C10") (pinfunction "PC10_C10") (pintype "bidirectional"))
    )
    (net (code "95") (name "unconnected-(U$4-PC11-PadC11)") (class "Default")
      (node (ref "U$4") (pin "C11") (pinfunction "PC11_C11") (pintype "bidirectional"))
    )
    (net (code "96") (name "unconnected-(U$4-PC12-PadC12)") (class "Default")
      (node (ref "U$4") (pin "C12") (pinfunction "PC12_C12") (pintype "bidirectional"))
    )
    (net (code "97") (name "unconnected-(U$4-PC13-PadC13)") (class "Default")
      (node (ref "U$4") (pin "C13") (pinfunction "PC13_C13") (pintype "bidirectional"))
    )
    (net (code "98") (name "unconnected-(U$4-PD1-PadD1)") (class "Default")
      (node (ref "U$4") (pin "D1") (pinfunction "PD1_D1") (pintype "bidirectional"))
    )
    (net (code "99") (name "unconnected-(U$4-PD2-PadD2)") (class "Default")
      (node (ref "U$4") (pin "D2") (pinfunction "PD2_D2") (pintype "bidirectional"))
    )
    (net (code "100") (name "unconnected-(U$4-PD3-PadD3)") (class "Default")
      (node (ref "U$4") (pin "D3") (pinfunction "PD3_D3") (pintype "bidirectional"))
    )
    (net (code "101") (name "unconnected-(U$4-PD4-PadD4)") (class "Default")
      (node (ref "U$4") (pin "D4") (pinfunction "PD4_D4") (pintype "bidirectional"))
    )
    (net (code "102") (name "unconnected-(U$4-PD5-PadD5)") (class "Default")
      (node (ref "U$4") (pin "D5") (pinfunction "PD5_D5") (pintype "bidirectional"))
    )
    (net (code "103") (name "unconnected-(U$4-PD6-PadD6)") (class "Default")
      (node (ref "U$4") (pin "D6") (pinfunction "PD6_D6") (pintype "bidirectional"))
    )
    (net (code "104") (name "unconnected-(U$4-PD7-PadD7)") (class "Default")
      (node (ref "U$4") (pin "D7") (pinfunction "PD7_D7") (pintype "bidirectional"))
    )
    (net (code "105") (name "unconnected-(U$4-PD8-PadD8)") (class "Default")
      (node (ref "U$4") (pin "D8") (pinfunction "PD8_D8") (pintype "bidirectional"))
    )
    (net (code "106") (name "unconnected-(U$4-PD9-PadD9)") (class "Default")
      (node (ref "U$4") (pin "D9") (pinfunction "PD9_D9") (pintype "bidirectional"))
    )
    (net (code "107") (name "unconnected-(U$4-PD10-PadD10)") (class "Default")
      (node (ref "U$4") (pin "D10") (pinfunction "PD10_D10") (pintype "bidirectional"))
    )
    (net (code "108") (name "unconnected-(U$4-PD11-PadD11)") (class "Default")
      (node (ref "U$4") (pin "D11") (pinfunction "PD11_D11") (pintype "bidirectional"))
    )
    (net (code "109") (name "unconnected-(U$4-PD12-PadD12)") (class "Default")
      (node (ref "U$4") (pin "D12") (pinfunction "PD12_D12") (pintype "bidirectional"))
    )
    (net (code "110") (name "unconnected-(U$4-PD13-PadD13)") (class "Default")
      (node (ref "U$4") (pin "D13") (pinfunction "PD13_D13") (pintype "bidirectional"))
    )
    (net (code "111") (name "unconnected-(U$4-PD14-PadD14)") (class "Default")
      (node (ref "U$4") (pin "D14") (pinfunction "PD14_D14") (pintype "bidirectional"))
    )
    (net (code "112") (name "unconnected-(U$4-PD15-PadD15)") (class "Default")
      (node (ref "U$4") (pin "D15") (pinfunction "PD15_D15") (pintype "bidirectional"))
    )
    (net (code "113") (name "unconnected-(U$4-PE3-PadE3)") (class "Default")
      (node (ref "U$4") (pin "E3") (pinfunction "PE3_E3") (pintype "bidirectional"))
    )
    (net (code "114") (name "unconnected-(U$4-PE7-PadE7)") (class "Default")
      (node (ref "U$4") (pin "E7") (pinfunction "PE7_E7") (pintype "bidirectional"))
    )
    (net (code "115") (name "unconnected-(U$4-PE8-PadE8)") (class "Default")
      (node (ref "U$4") (pin "E8") (pinfunction "PE8_E8") (pintype "bidirectional"))
    )
    (net (code "116") (name "unconnected-(U$4-PE9-PadE9)") (class "Default")
      (node (ref "U$4") (pin "E9") (pinfunction "PE9_E9") (pintype "bidirectional"))
    )
    (net (code "117") (name "unconnected-(U$4-PE10-PadE10)") (class "Default")
      (node (ref "U$4") (pin "E10") (pinfunction "PE10_E10") (pintype "bidirectional"))
    )
    (net (code "118") (name "unconnected-(U$4-PE11-PadE11)") (class "Default")
      (node (ref "U$4") (pin "E11") (pinfunction "PE11_E11") (pintype "bidirectional"))
    )
    (net (code "119") (name "unconnected-(U$4-PE12-PadE12)") (class "Default")
      (node (ref "U$4") (pin "E12") (pinfunction "PE12_E12") (pintype "bidirectional"))
    )
    (net (code "120") (name "unconnected-(U$4-PE13-PadE13)") (class "Default")
      (node (ref "U$4") (pin "E13") (pinfunction "PE13_E13") (pintype "bidirectional"))
    )
    (net (code "121") (name "unconnected-(U$4-PE14-PadE14)") (class "Default")
      (node (ref "U$4") (pin "E14") (pinfunction "PE14_E14") (pintype "bidirectional"))
    )
    (net (code "122") (name "unconnected-(U$4-PadV+)") (class "Default")
      (node (ref "U$4") (pin "V+") (pinfunction "V+_V+") (pintype "bidirectional"))
    )
    (net (code "123") (name "unconnected-(U$4-VBAT-PadVB)") (class "Default")
      (node (ref "U$4") (pin "VB") (pinfunction "VBAT_VB") (pintype "bidirectional"))
    )
    (net (code "124") (name "unconnected-(U$7A-CW-Pad3)") (class "Default")
      (node (ref "U$7") (pin "3") (pinfunction "CW_3") (pintype "passive"))
    )
    (net (code "125") (name "unconnected-(U$7B-CCW-Pad4)") (class "Default")
      (node (ref "U$7") (pin "4") (pinfunction "CCW_4") (pintype "passive"))
    )
  )
)
